# extension_dfplayer.net
KiCad netlist of a schematic drawn in EasyEDA
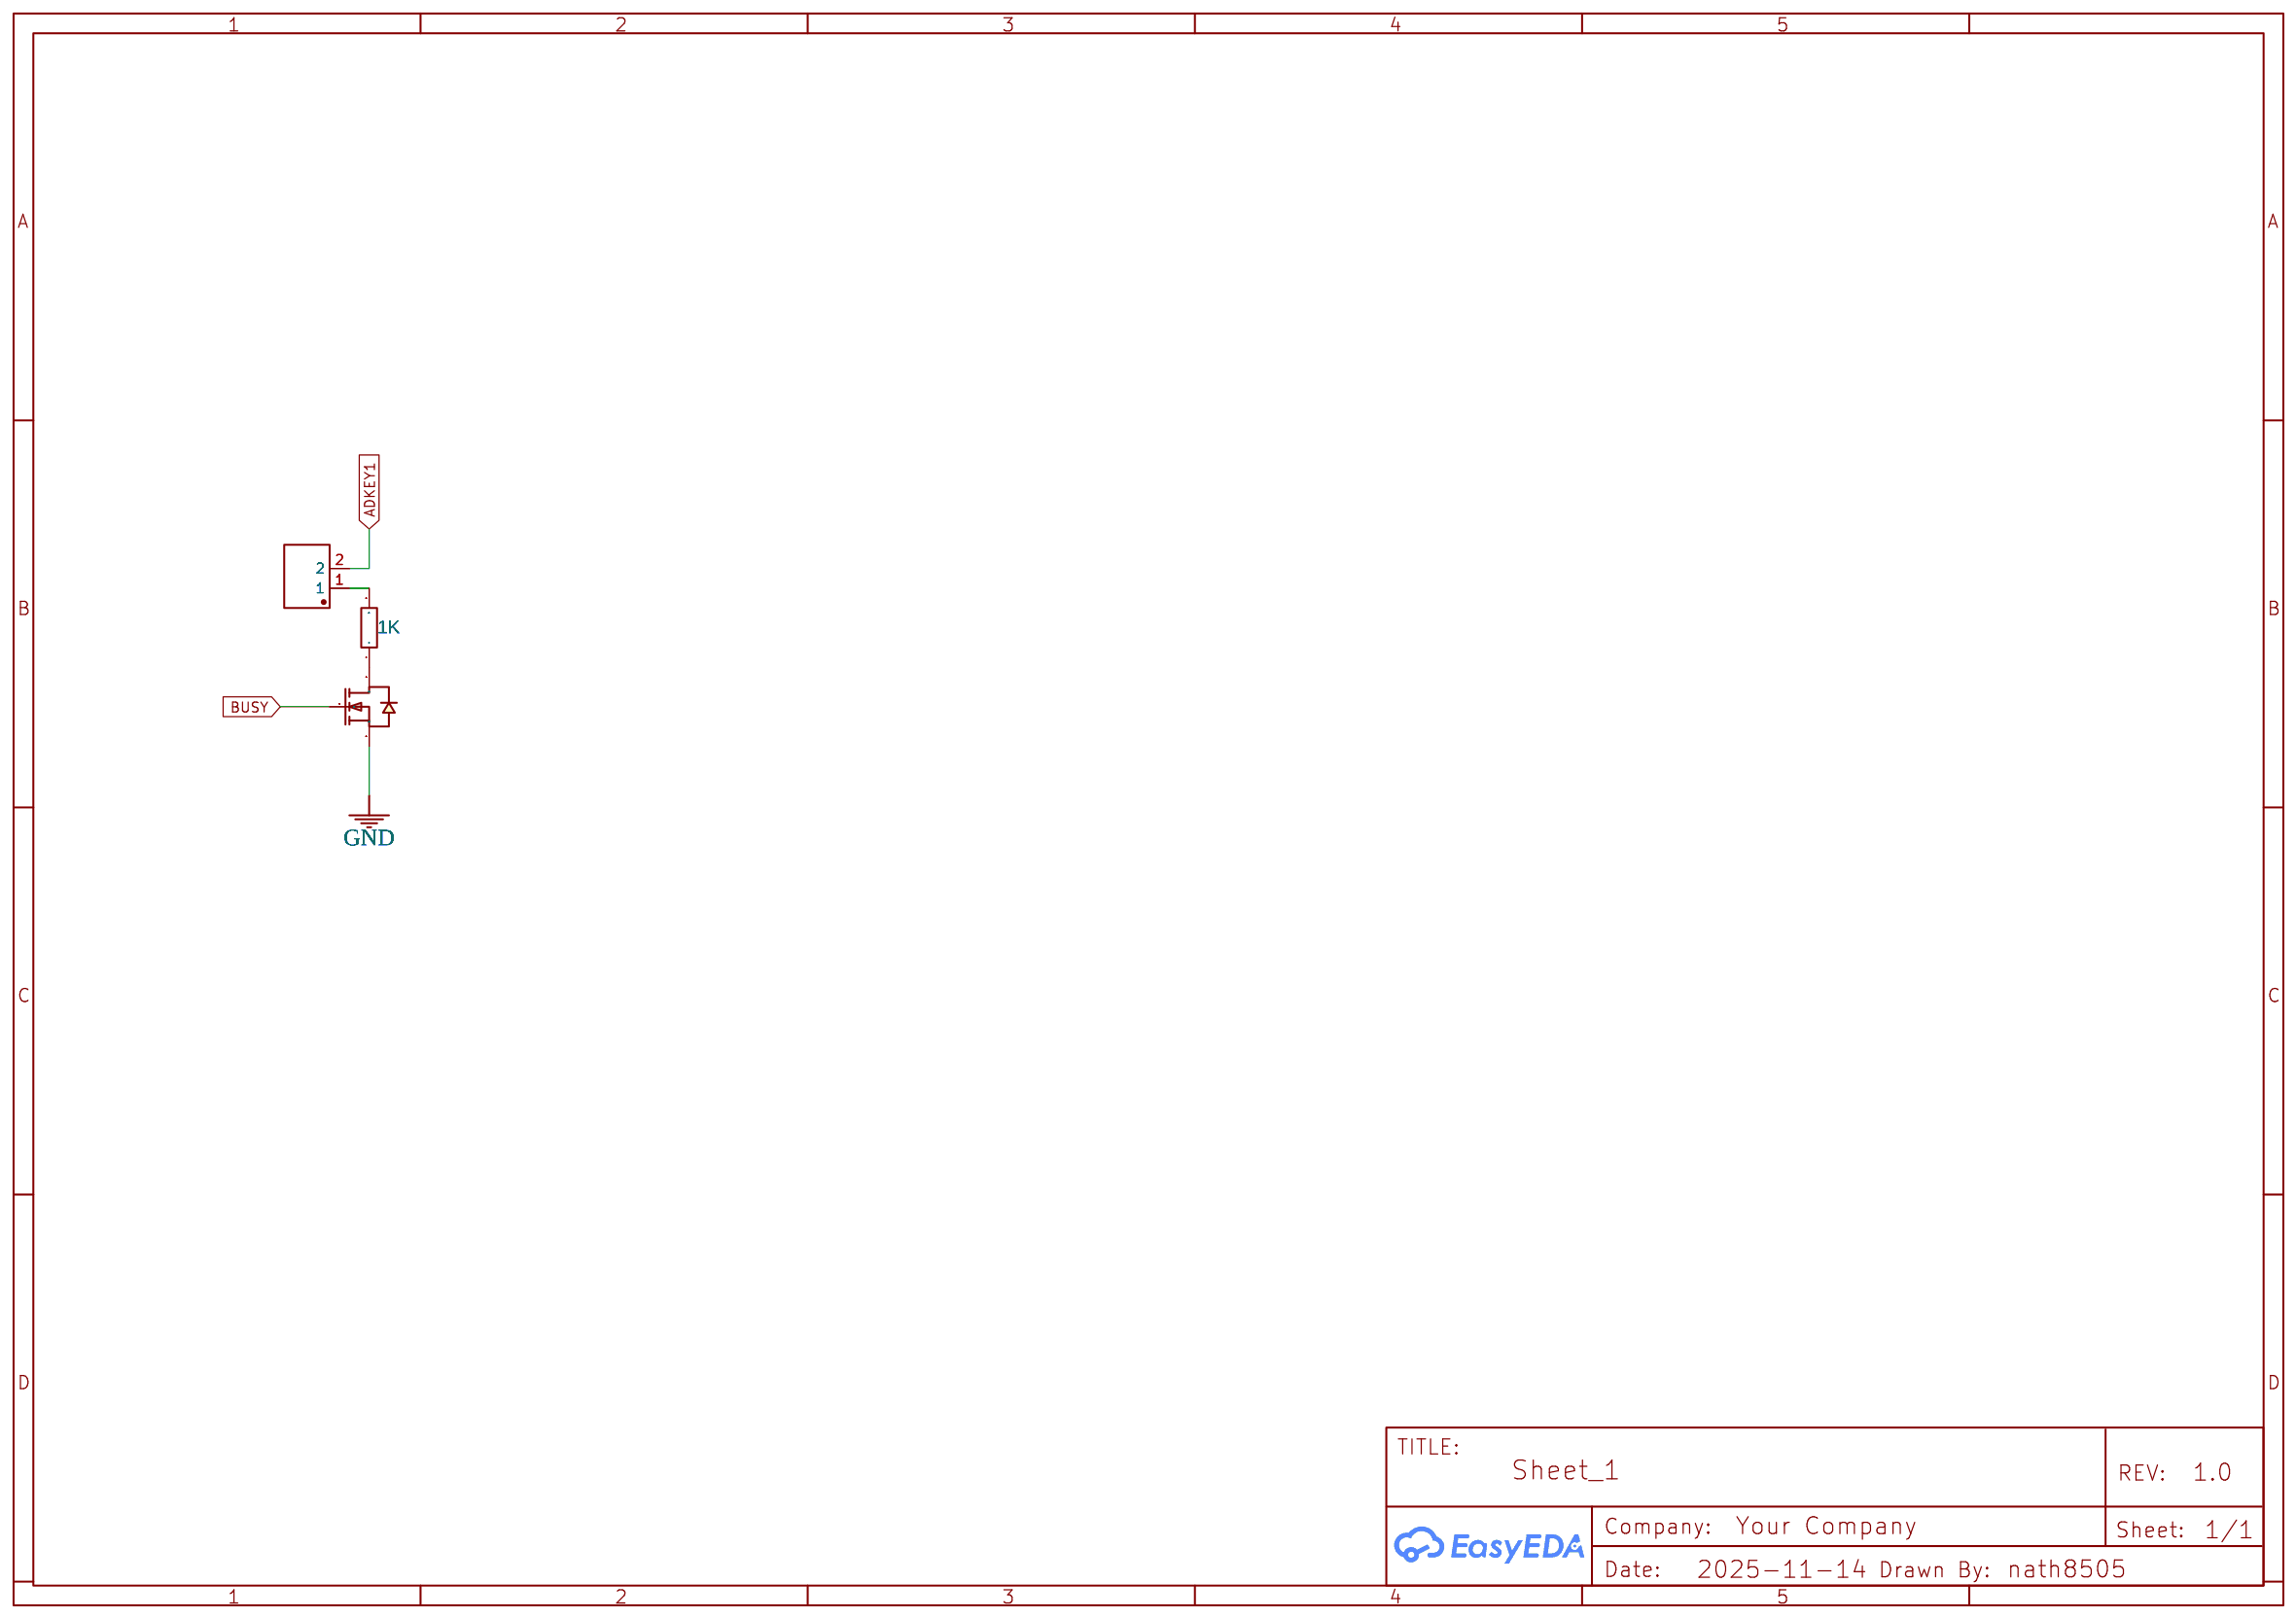
[diagram p0: schematic sheet]

(export (version "E")
  (design (tool "Eeschema 10.0.6"))
  (components
    (comp (ref "ECON1")
      (value "D_OUT8")
      (fields (field (name "Manufacturer Part") "KF2510-2A") (field (name "Manufacturer") "BOOMELE"))
      (libsource (lib "") (part "KF2510-2A"))
    )
    (comp (ref "EQ1")
      (value "Q")
      (fields (field (name "Manufacturer Part") "AO3400") (field (name "Manufacturer") "ElecSuper(静芯微）"))
      (libsource (lib "") (part "JSM2302"))
    )
    (comp (ref "ERL1")
      (value "1K")
      (fields (field (name "Manufacturer Part") "0603WAF1001T5E") (field (name "Manufacturer") "UniOhm"))
      (libsource (lib "") (part "0603WAF1001T5E"))
    )
  )
  (nets
    (net (code "1") (name "ADKEY1") (class "Default")
      (node (ref "ECON1") (pin "2") (pinfunction "2_2") (pintype "unspecified"))
    )
    (net (code "2") (name "BUSY") (class "Default")
      (node (ref "EQ1") (pin "1") (pinfunction "G_1") (pintype "unspecified"))
    )
    (net (code "3") (name "GND") (class "Default")
      (node (ref "EQ1") (pin "2") (pinfunction "S_2") (pintype "unspecified"))
    )
    (net (code "4") (name "Net-(ECON1-Pad1)") (class "Default")
      (node (ref "ECON1") (pin "1") (pinfunction "1_1") (pintype "unspecified"))
      (node (ref "ERL1") (pin "2") (pinfunction "2_2") (pintype "input"))
    )
    (net (code "5") (name "Net-(EQ1-D)") (class "Default")
      (node (ref "EQ1") (pin "3") (pinfunction "D_3") (pintype "unspecified"))
      (node (ref "ERL1") (pin "1") (pinfunction "1_1") (pintype "input"))
    )
  )
)
